# devboard_kw2xd_v1_0.net
KiCad netlist of a schematic drawn in EAGLE
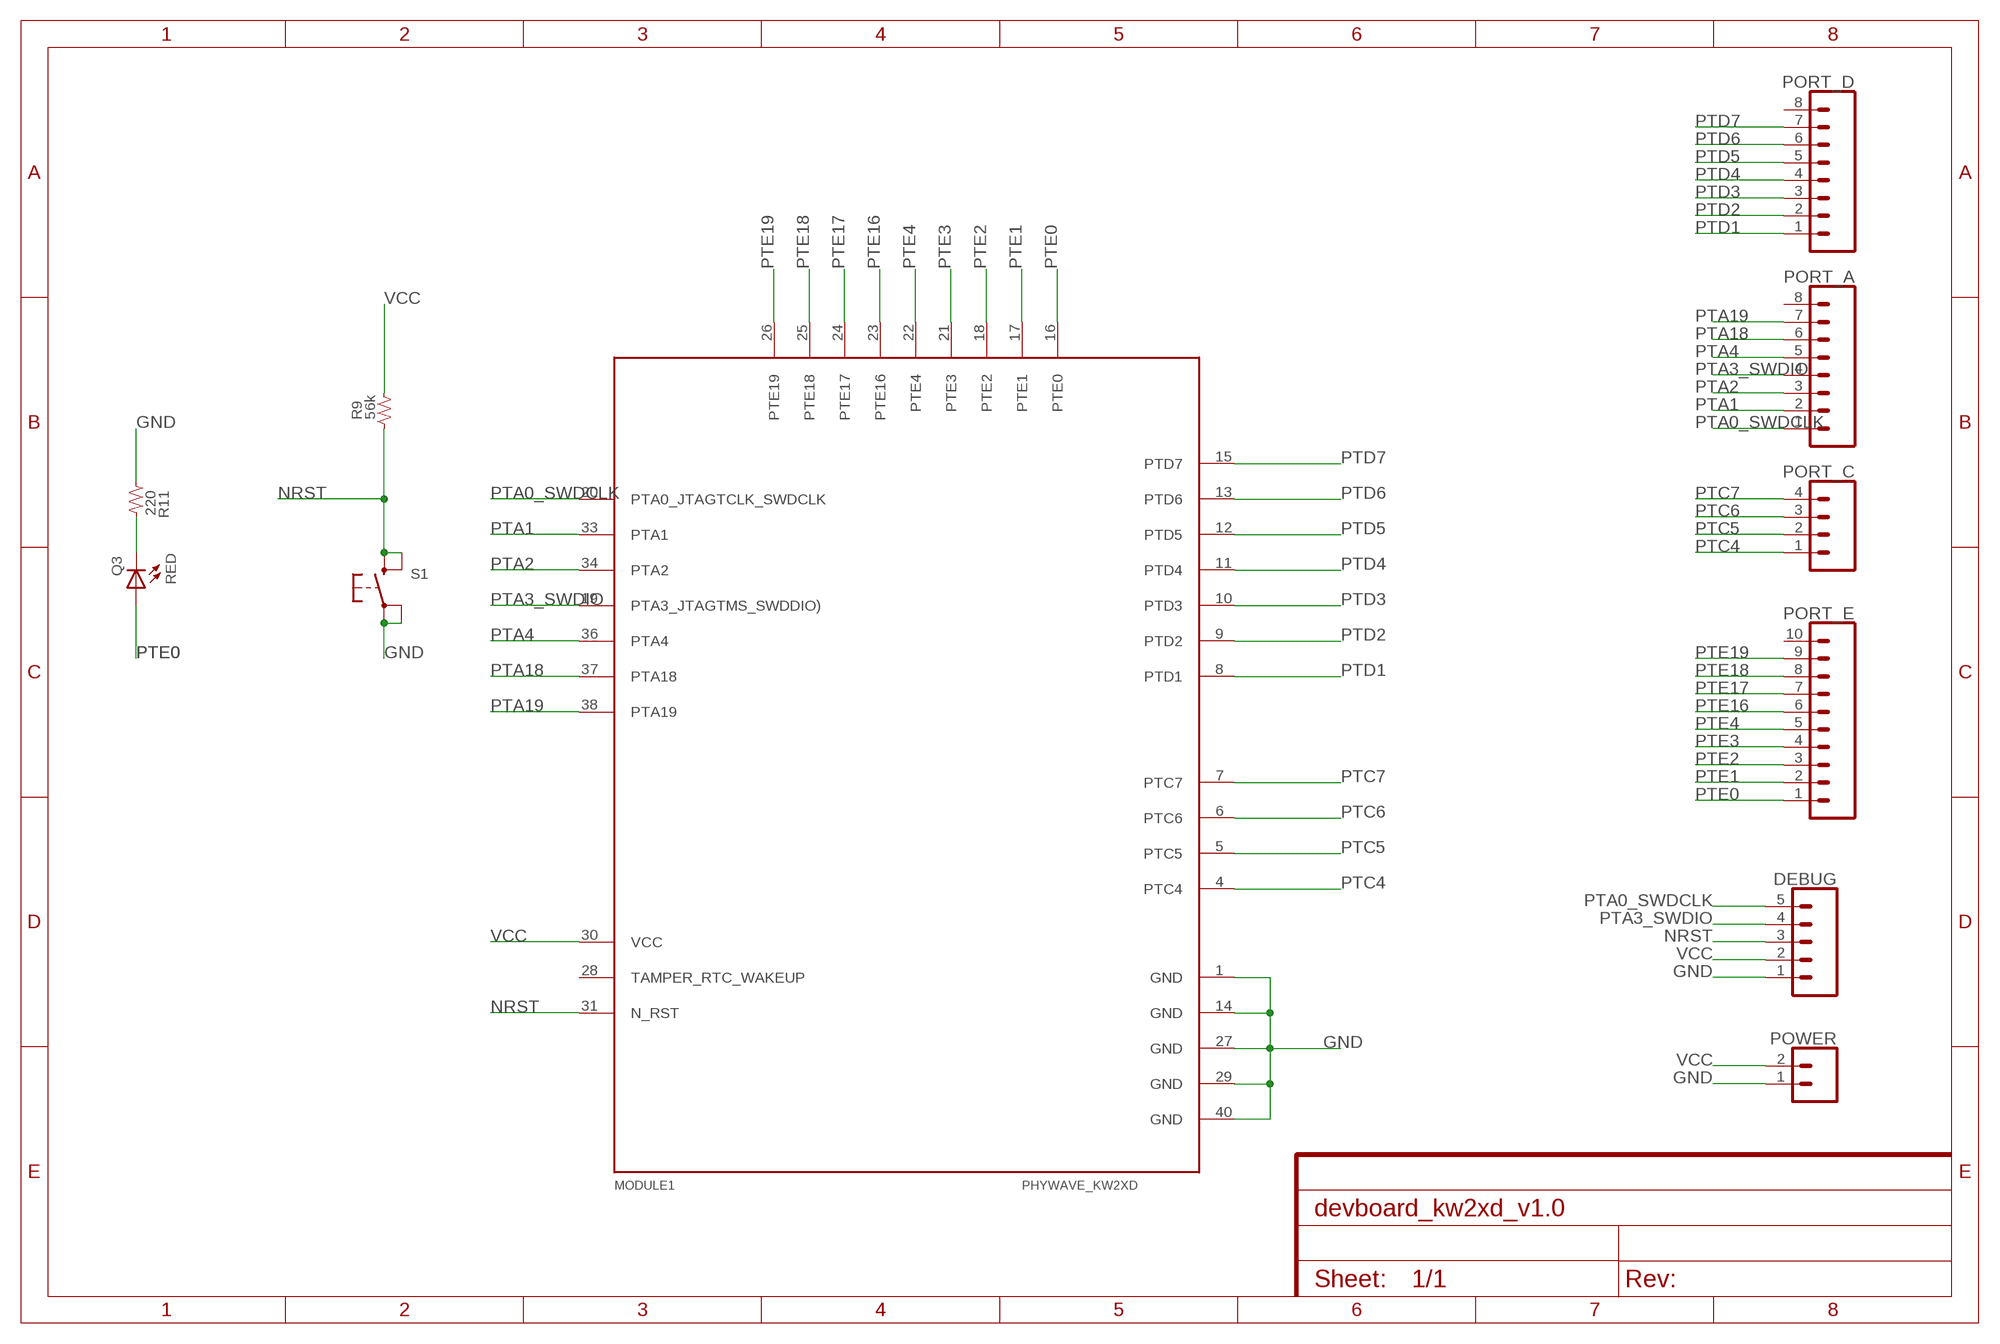
[diagram p0: schematic, sheet 1]

(export (version "E")
  (design (tool "Eeschema 10.0.6"))
  (components
    (comp (ref "DEBUG")
      (value "CONN_05")
      (footprint "eagle-import:1X05")
      (libsource (lib "eagle-import") (part "CONN_05"))
    )
    (comp (ref "MODULE1")
      (value "PHYWAVE_KW2XD")
      (footprint "eagle-import:PHYWAVE_KW2XD")
      (libsource (lib "eagle-import") (part "PHYWAVE_KW2XD"))
    )
    (comp (ref "PORT_A")
      (value "CONN_08\"")
      (footprint "eagle-import:1X08")
      (libsource (lib "eagle-import") (part "CONN_08{dblquote}"))
    )
    (comp (ref "PORT_C")
      (value "CONN_04")
      (footprint "eagle-import:1X04")
      (libsource (lib "eagle-import") (part "CONN_04"))
    )
    (comp (ref "PORT_D")
      (value "CONN_08\"")
      (footprint "eagle-import:1X08")
      (libsource (lib "eagle-import") (part "CONN_08{dblquote}"))
    )
    (comp (ref "PORT_E")
      (value "CONN_10\"")
      (footprint "eagle-import:1X10")
      (libsource (lib "eagle-import") (part "CONN_10{dblquote}"))
    )
    (comp (ref "POWER")
      (value "CONN_02")
      (footprint "eagle-import:1X02")
      (libsource (lib "eagle-import") (part "CONN_02"))
    )
    (comp (ref "Q3")
      (value "RED")
      (footprint "eagle-import:LED0603")
      (libsource (lib "eagle-import") (part "LED-0603"))
    )
    (comp (ref "R9")
      (value "56k")
      (footprint "eagle-import:SMD0603")
      (libsource (lib "eagle-import") (part "R-0603"))
    )
    (comp (ref "R11")
      (value "220")
      (footprint "eagle-import:SMD0603")
      (libsource (lib "eagle-import") (part "R-0603"))
    )
    (comp (ref "S1")
      (value "SPST-MOM-KSCJ")
      (footprint "eagle-import:KSC-J")
      (libsource (lib "eagle-import") (part "SPST-MOM-KSCJ"))
    )
  )
  (nets
    (net (code "1") (name "/GND") (class "Default")
      (node (ref "DEBUG") (pin "1") (pinfunction "1_1") (pintype "passive"))
      (node (ref "MODULE1") (pin "1") (pinfunction "GND_1") (pintype "bidirectional"))
      (node (ref "MODULE1") (pin "14") (pinfunction "GND_14") (pintype "bidirectional"))
      (node (ref "MODULE1") (pin "27") (pinfunction "GND_27") (pintype "bidirectional"))
      (node (ref "MODULE1") (pin "29") (pinfunction "GND_29") (pintype "bidirectional"))
      (node (ref "MODULE1") (pin "40") (pinfunction "GND_40") (pintype "bidirectional"))
      (node (ref "POWER") (pin "1") (pinfunction "1_1") (pintype "passive"))
      (node (ref "R11") (pin "1") (pinfunction "1_1") (pintype "passive"))
      (node (ref "S1") (pin "A1") (pinfunction "P_A1") (pintype "passive"))
      (node (ref "S1") (pin "A2") (pinfunction "P1_A2") (pintype "passive"))
    )
    (net (code "2") (name "/NRST") (class "Default")
      (node (ref "DEBUG") (pin "3") (pinfunction "3_3") (pintype "passive"))
      (node (ref "MODULE1") (pin "31") (pinfunction "N_RST_31") (pintype "bidirectional"))
      (node (ref "R9") (pin "1") (pinfunction "1_1") (pintype "passive"))
      (node (ref "S1") (pin "B1") (pinfunction "S_B1") (pintype "passive"))
      (node (ref "S1") (pin "B2") (pinfunction "S1_B2") (pintype "passive"))
    )
    (net (code "3") (name "/PTA0_SWDCLK") (class "Default")
      (node (ref "DEBUG") (pin "5") (pinfunction "5_5") (pintype "passive"))
      (node (ref "MODULE1") (pin "20") (pinfunction "PTA0_JTAGTCLK_SWDCLK_20") (pintype "bidirectional"))
      (node (ref "PORT_A") (pin "1") (pinfunction "1_1") (pintype "passive"))
    )
    (net (code "4") (name "/PTA1") (class "Default")
      (node (ref "MODULE1") (pin "33") (pinfunction "PTA1_33") (pintype "bidirectional"))
      (node (ref "PORT_A") (pin "2") (pinfunction "2_2") (pintype "passive"))
    )
    (net (code "5") (name "/PTA2") (class "Default")
      (node (ref "MODULE1") (pin "34") (pinfunction "PTA2_34") (pintype "bidirectional"))
      (node (ref "PORT_A") (pin "3") (pinfunction "3_3") (pintype "passive"))
    )
    (net (code "6") (name "/PTA3_SWDIO") (class "Default")
      (node (ref "DEBUG") (pin "4") (pinfunction "4_4") (pintype "passive"))
      (node (ref "MODULE1") (pin "19") (pinfunction "PTA3_JTAGTMS_SWDDIO)_19") (pintype "bidirectional"))
      (node (ref "PORT_A") (pin "4") (pinfunction "4_4") (pintype "passive"))
    )
    (net (code "7") (name "/PTA4") (class "Default")
      (node (ref "MODULE1") (pin "36") (pinfunction "PTA4_36") (pintype "bidirectional"))
      (node (ref "PORT_A") (pin "5") (pinfunction "5_5") (pintype "passive"))
    )
    (net (code "8") (name "/PTA18") (class "Default")
      (node (ref "MODULE1") (pin "37") (pinfunction "PTA18_37") (pintype "bidirectional"))
      (node (ref "PORT_A") (pin "6") (pinfunction "6_6") (pintype "passive"))
    )
    (net (code "9") (name "/PTA19") (class "Default")
      (node (ref "MODULE1") (pin "38") (pinfunction "PTA19_38") (pintype "bidirectional"))
      (node (ref "PORT_A") (pin "7") (pinfunction "7_7") (pintype "passive"))
    )
    (net (code "10") (name "/PTC4") (class "Default")
      (node (ref "MODULE1") (pin "4") (pinfunction "PTC4_4") (pintype "bidirectional"))
      (node (ref "PORT_C") (pin "1") (pinfunction "1_1") (pintype "passive"))
    )
    (net (code "11") (name "/PTC5") (class "Default")
      (node (ref "MODULE1") (pin "5") (pinfunction "PTC5_5") (pintype "bidirectional"))
      (node (ref "PORT_C") (pin "2") (pinfunction "2_2") (pintype "passive"))
    )
    (net (code "12") (name "/PTC6") (class "Default")
      (node (ref "MODULE1") (pin "6") (pinfunction "PTC6_6") (pintype "bidirectional"))
      (node (ref "PORT_C") (pin "3") (pinfunction "3_3") (pintype "passive"))
    )
    (net (code "13") (name "/PTC7") (class "Default")
      (node (ref "MODULE1") (pin "7") (pinfunction "PTC7_7") (pintype "bidirectional"))
      (node (ref "PORT_C") (pin "4") (pinfunction "4_4") (pintype "passive"))
    )
    (net (code "14") (name "/PTD1") (class "Default")
      (node (ref "MODULE1") (pin "8") (pinfunction "PTD1_8") (pintype "bidirectional"))
      (node (ref "PORT_D") (pin "1") (pinfunction "1_1") (pintype "passive"))
    )
    (net (code "15") (name "/PTD2") (class "Default")
      (node (ref "MODULE1") (pin "9") (pinfunction "PTD2_9") (pintype "bidirectional"))
      (node (ref "PORT_D") (pin "2") (pinfunction "2_2") (pintype "passive"))
    )
    (net (code "16") (name "/PTD3") (class "Default")
      (node (ref "MODULE1") (pin "10") (pinfunction "PTD3_10") (pintype "bidirectional"))
      (node (ref "PORT_D") (pin "3") (pinfunction "3_3") (pintype "passive"))
    )
    (net (code "17") (name "/PTD4") (class "Default")
      (node (ref "MODULE1") (pin "11") (pinfunction "PTD4_11") (pintype "bidirectional"))
      (node (ref "PORT_D") (pin "4") (pinfunction "4_4") (pintype "passive"))
    )
    (net (code "18") (name "/PTD5") (class "Default")
      (node (ref "MODULE1") (pin "12") (pinfunction "PTD5_12") (pintype "bidirectional"))
      (node (ref "PORT_D") (pin "5") (pinfunction "5_5") (pintype "passive"))
    )
    (net (code "19") (name "/PTD6") (class "Default")
      (node (ref "MODULE1") (pin "13") (pinfunction "PTD6_13") (pintype "bidirectional"))
      (node (ref "PORT_D") (pin "6") (pinfunction "6_6") (pintype "passive"))
    )
    (net (code "20") (name "/PTD7") (class "Default")
      (node (ref "MODULE1") (pin "15") (pinfunction "PTD7_15") (pintype "bidirectional"))
      (node (ref "PORT_D") (pin "7") (pinfunction "7_7") (pintype "passive"))
    )
    (net (code "21") (name "/PTE0") (class "Default")
      (node (ref "MODULE1") (pin "16") (pinfunction "PTE0_16") (pintype "bidirectional"))
      (node (ref "PORT_E") (pin "1") (pinfunction "1_1") (pintype "passive"))
      (node (ref "Q3") (pin "A") (pinfunction "A_A") (pintype "passive"))
    )
    (net (code "22") (name "/PTE1") (class "Default")
      (node (ref "MODULE1") (pin "17") (pinfunction "PTE1_17") (pintype "bidirectional"))
      (node (ref "PORT_E") (pin "2") (pinfunction "2_2") (pintype "passive"))
    )
    (net (code "23") (name "/PTE2") (class "Default")
      (node (ref "MODULE1") (pin "18") (pinfunction "PTE2_18") (pintype "bidirectional"))
      (node (ref "PORT_E") (pin "3") (pinfunction "3_3") (pintype "passive"))
    )
    (net (code "24") (name "/PTE3") (class "Default")
      (node (ref "MODULE1") (pin "21") (pinfunction "PTE3_21") (pintype "bidirectional"))
      (node (ref "PORT_E") (pin "4") (pinfunction "4_4") (pintype "passive"))
    )
    (net (code "25") (name "/PTE4") (class "Default")
      (node (ref "MODULE1") (pin "22") (pinfunction "PTE4_22") (pintype "bidirectional"))
      (node (ref "PORT_E") (pin "5") (pinfunction "5_5") (pintype "passive"))
    )
    (net (code "26") (name "/PTE16") (class "Default")
      (node (ref "MODULE1") (pin "23") (pinfunction "PTE16_23") (pintype "bidirectional"))
      (node (ref "PORT_E") (pin "6") (pinfunction "6_6") (pintype "passive"))
    )
    (net (code "27") (name "/PTE17") (class "Default")
      (node (ref "MODULE1") (pin "24") (pinfunction "PTE17_24") (pintype "bidirectional"))
      (node (ref "PORT_E") (pin "7") (pinfunction "7_7") (pintype "passive"))
    )
    (net (code "28") (name "/PTE18") (class "Default")
      (node (ref "MODULE1") (pin "25") (pinfunction "PTE18_25") (pintype "bidirectional"))
      (node (ref "PORT_E") (pin "8") (pinfunction "8_8") (pintype "passive"))
    )
    (net (code "29") (name "/PTE19") (class "Default")
      (node (ref "MODULE1") (pin "26") (pinfunction "PTE19_26") (pintype "bidirectional"))
      (node (ref "PORT_E") (pin "9") (pinfunction "9_9") (pintype "passive"))
    )
    (net (code "30") (name "/VCC") (class "Default")
      (node (ref "DEBUG") (pin "2") (pinfunction "2_2") (pintype "passive"))
      (node (ref "MODULE1") (pin "30") (pinfunction "VCC_30") (pintype "bidirectional"))
      (node (ref "POWER") (pin "2") (pinfunction "2_2") (pintype "passive"))
      (node (ref "R9") (pin "2") (pinfunction "2_2") (pintype "passive"))
    )
    (net (code "31") (name "Net-(Q3-PadC)") (class "Default")
      (node (ref "Q3") (pin "C") (pinfunction "C_C") (pintype "passive"))
      (node (ref "R11") (pin "2") (pinfunction "2_2") (pintype "passive"))
    )
    (net (code "32") (name "unconnected-(MODULE1-TAMPER_RTC_WAKEUP-Pad28)") (class "Default")
      (node (ref "MODULE1") (pin "28") (pinfunction "TAMPER_RTC_WAKEUP_28") (pintype "bidirectional"))
    )
    (net (code "33") (name "unconnected-(PORT_A-Pad8)") (class "Default")
      (node (ref "PORT_A") (pin "8") (pinfunction "8_8") (pintype "passive"))
    )
    (net (code "34") (name "unconnected-(PORT_D-Pad8)") (class "Default")
      (node (ref "PORT_D") (pin "8") (pinfunction "8_8") (pintype "passive"))
    )
    (net (code "35") (name "unconnected-(PORT_E-Pad10)") (class "Default")
      (node (ref "PORT_E") (pin "10") (pinfunction "10_10") (pintype "passive"))
    )
  )
)
